# BQSandBox.net
KiCad netlist of a schematic drawn in Altium Designer
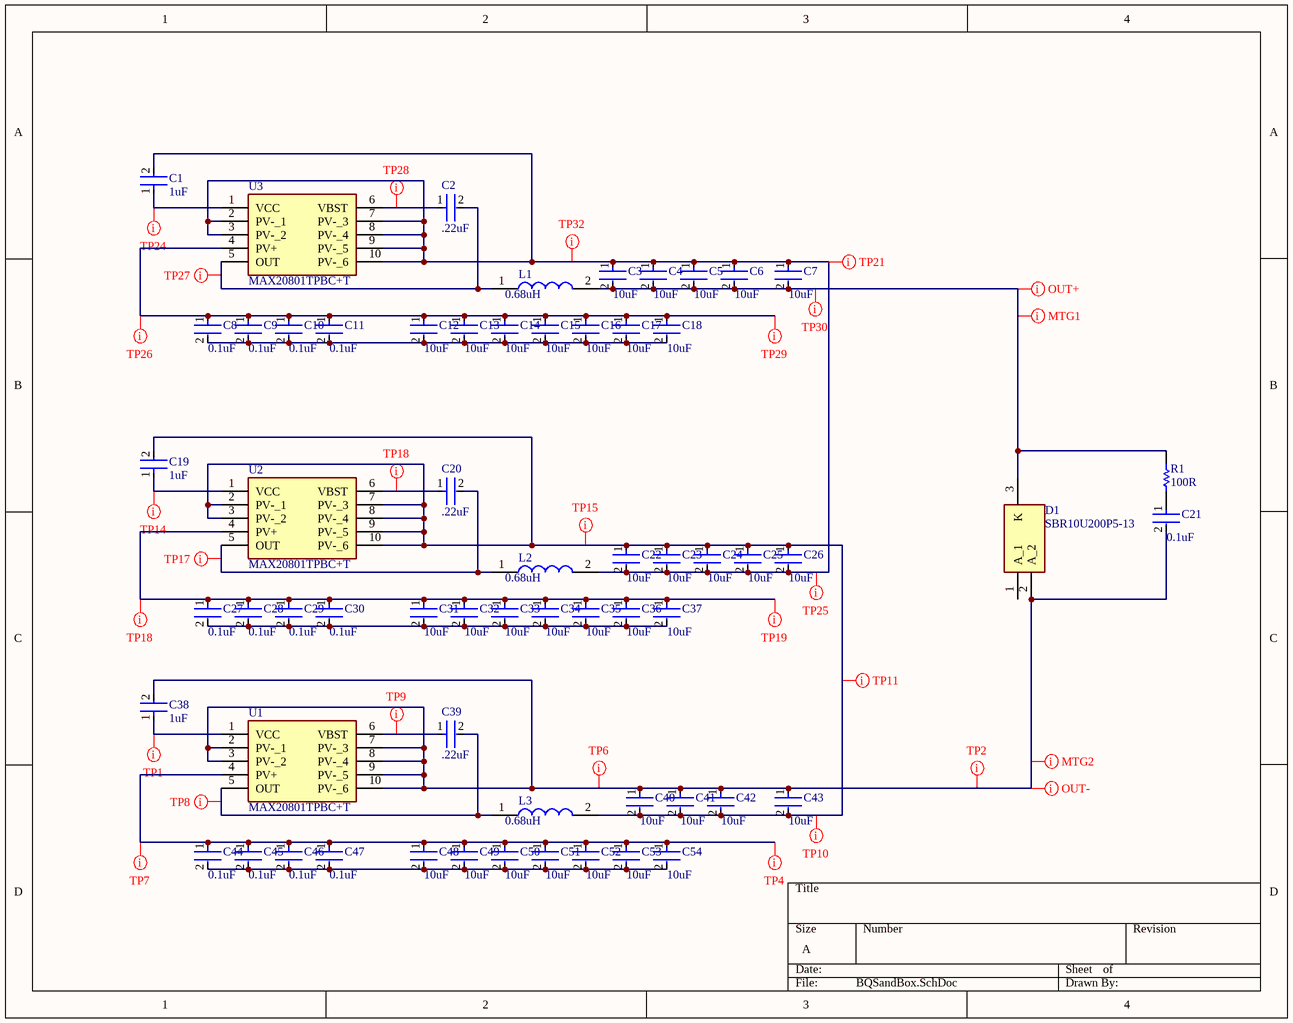
[diagram p0: BQSandBox.SchDoc]

(export (version "E")
  (design (tool "Eeschema 10.0.6"))
  (components
    (comp (ref "C1")
      (value "1uF")
      (footprint "FP-C0805C-DN-IPC_A")
      (description "Cap Ceramic 1uF 16V X5R 10% SMD 0805 85C Plastic T/R")
      (fields
        (field (name "MANUFACTURER") "KEMET")
        (field (name "MANUFACTURER PART NUMBER") "C0805C105K4PACTU")
      )
      (libsource (lib "WEST_Schematic_Library") (part "C0805C105K4PACTU"))
    )
    (comp (ref "C2")
      (value ".22uF")
      (footprint "FP-C0805C-DN-MFG")
      (description "C0805 0.22 μF X7R 30ppm/°C 10.00% 50 V")
      (fields (field (name "MANUFACTURER") "KEMET"))
      (libsource (lib "Altium Content Vault") (part "b4654b650e69147ec39a6b967a45e02"))
    )
    (comp (ref "C3")
      (value "10uF")
      (footprint "FP-C0805C-DN-IPC_A")
      (description "贴片电容（MLCC） 10μF ±10% 16V X5R 0805")
      (fields
        (field (name "MANUFACTURER") "Murata")
        (field (name "MANUFACTURER PART NUMBER") "GRM21BR61C106KE15L")
      )
      (libsource (lib "WEST_Schematic_Library") (part "GRM21BR61C106KE15L"))
    )
    (comp (ref "C4")
      (value "10uF")
      (footprint "FP-C0805C-DN-IPC_A")
      (description "贴片电容（MLCC） 10μF ±10% 16V X5R 0805")
      (fields
        (field (name "MANUFACTURER") "Murata")
        (field (name "MANUFACTURER PART NUMBER") "GRM21BR61C106KE15L")
      )
      (libsource (lib "WEST_Schematic_Library") (part "GRM21BR61C106KE15L"))
    )
    (comp (ref "C5")
      (value "10uF")
      (footprint "FP-C0805C-DN-IPC_A")
      (description "贴片电容（MLCC） 10μF ±10% 16V X5R 0805")
      (fields
        (field (name "MANUFACTURER") "Murata")
        (field (name "MANUFACTURER PART NUMBER") "GRM21BR61C106KE15L")
      )
      (libsource (lib "WEST_Schematic_Library") (part "GRM21BR61C106KE15L"))
    )
    (comp (ref "C6")
      (value "10uF")
      (footprint "FP-C0805C-DN-IPC_A")
      (description "贴片电容（MLCC） 10μF ±10% 16V X5R 0805")
      (fields
        (field (name "MANUFACTURER") "Murata")
        (field (name "MANUFACTURER PART NUMBER") "GRM21BR61C106KE15L")
      )
      (libsource (lib "WEST_Schematic_Library") (part "GRM21BR61C106KE15L"))
    )
    (comp (ref "C7")
      (value "10uF")
      (footprint "FP-C0805C-DN-IPC_A")
      (description "贴片电容（MLCC） 10μF ±10% 16V X5R 0805")
      (fields
        (field (name "MANUFACTURER") "Murata")
        (field (name "MANUFACTURER PART NUMBER") "GRM21BR61C106KE15L")
      )
      (libsource (lib "WEST_Schematic_Library") (part "GRM21BR61C106KE15L"))
    )
    (comp (ref "C8")
      (value "0.1uF")
      (footprint "FP-C0805C-DN-IPC_A")
      (description "Cap Ceramic 0.1uF 50V X7R 10% SMD 2.0 x 1.2 mm 125 C Paper T/R")
      (fields
        (field (name "MANUFACTURER") "KEMET")
        (field (name "MANUFACTURER PART NUMBER") "C0805C104K5RACTU")
      )
      (libsource (lib "WEST_Schematic_Library") (part "C0805C104K5RACTU"))
    )
    (comp (ref "C9")
      (value "0.1uF")
      (footprint "FP-C0805C-DN-IPC_A")
      (description "Cap Ceramic 0.1uF 50V X7R 10% SMD 2.0 x 1.2 mm 125 C Paper T/R")
      (fields
        (field (name "MANUFACTURER") "KEMET")
        (field (name "MANUFACTURER PART NUMBER") "C0805C104K5RACTU")
      )
      (libsource (lib "WEST_Schematic_Library") (part "C0805C104K5RACTU"))
    )
    (comp (ref "C10")
      (value "0.1uF")
      (footprint "FP-C0805C-DN-IPC_A")
      (description "Cap Ceramic 0.1uF 50V X7R 10% SMD 2.0 x 1.2 mm 125 C Paper T/R")
      (fields
        (field (name "MANUFACTURER") "KEMET")
        (field (name "MANUFACTURER PART NUMBER") "C0805C104K5RACTU")
      )
      (libsource (lib "WEST_Schematic_Library") (part "C0805C104K5RACTU"))
    )
    (comp (ref "C11")
      (value "0.1uF")
      (footprint "FP-C0805C-DN-IPC_A")
      (description "Cap Ceramic 0.1uF 50V X7R 10% SMD 2.0 x 1.2 mm 125 C Paper T/R")
      (fields
        (field (name "MANUFACTURER") "KEMET")
        (field (name "MANUFACTURER PART NUMBER") "C0805C104K5RACTU")
      )
      (libsource (lib "WEST_Schematic_Library") (part "C0805C104K5RACTU"))
    )
    (comp (ref "C12")
      (value "10uF")
      (footprint "FP-C0805C-DN-IPC_A")
      (description "贴片电容（MLCC） 10μF ±10% 16V X5R 0805")
      (fields
        (field (name "MANUFACTURER") "Murata")
        (field (name "MANUFACTURER PART NUMBER") "GRM21BR61C106KE15L")
      )
      (libsource (lib "WEST_Schematic_Library") (part "GRM21BR61C106KE15L"))
    )
    (comp (ref "C13")
      (value "10uF")
      (footprint "FP-C0805C-DN-IPC_A")
      (description "贴片电容（MLCC） 10μF ±10% 16V X5R 0805")
      (fields
        (field (name "MANUFACTURER") "Murata")
        (field (name "MANUFACTURER PART NUMBER") "GRM21BR61C106KE15L")
      )
      (libsource (lib "WEST_Schematic_Library") (part "GRM21BR61C106KE15L"))
    )
    (comp (ref "C14")
      (value "10uF")
      (footprint "FP-C0805C-DN-IPC_A")
      (description "贴片电容（MLCC） 10μF ±10% 16V X5R 0805")
      (fields
        (field (name "MANUFACTURER") "Murata")
        (field (name "MANUFACTURER PART NUMBER") "GRM21BR61C106KE15L")
      )
      (libsource (lib "WEST_Schematic_Library") (part "GRM21BR61C106KE15L"))
    )
    (comp (ref "C15")
      (value "10uF")
      (footprint "FP-C0805C-DN-IPC_A")
      (description "贴片电容（MLCC） 10μF ±10% 16V X5R 0805")
      (fields
        (field (name "MANUFACTURER") "Murata")
        (field (name "MANUFACTURER PART NUMBER") "GRM21BR61C106KE15L")
      )
      (libsource (lib "WEST_Schematic_Library") (part "GRM21BR61C106KE15L"))
    )
    (comp (ref "C16")
      (value "10uF")
      (footprint "FP-C0805C-DN-IPC_A")
      (description "贴片电容（MLCC） 10μF ±10% 16V X5R 0805")
      (fields
        (field (name "MANUFACTURER") "Murata")
        (field (name "MANUFACTURER PART NUMBER") "GRM21BR61C106KE15L")
      )
      (libsource (lib "WEST_Schematic_Library") (part "GRM21BR61C106KE15L"))
    )
    (comp (ref "C17")
      (value "10uF")
      (footprint "FP-C0805C-DN-IPC_A")
      (description "贴片电容（MLCC） 10μF ±10% 16V X5R 0805")
      (fields
        (field (name "MANUFACTURER") "Murata")
        (field (name "MANUFACTURER PART NUMBER") "GRM21BR61C106KE15L")
      )
      (libsource (lib "WEST_Schematic_Library") (part "GRM21BR61C106KE15L"))
    )
    (comp (ref "C18")
      (value "10uF")
      (footprint "FP-C0805C-DN-IPC_A")
      (description "贴片电容（MLCC） 10μF ±10% 16V X5R 0805")
      (fields
        (field (name "MANUFACTURER") "Murata")
        (field (name "MANUFACTURER PART NUMBER") "GRM21BR61C106KE15L")
      )
      (libsource (lib "WEST_Schematic_Library") (part "GRM21BR61C106KE15L"))
    )
    (comp (ref "C19")
      (value "1uF")
      (footprint "FP-C0805C-DN-IPC_A")
      (description "Cap Ceramic 1uF 16V X5R 10% SMD 0805 85C Plastic T/R")
      (fields
        (field (name "MANUFACTURER") "KEMET")
        (field (name "MANUFACTURER PART NUMBER") "C0805C105K4PACTU")
      )
      (libsource (lib "WEST_Schematic_Library") (part "C0805C105K4PACTU"))
    )
    (comp (ref "C20")
      (value ".22uF")
      (footprint "FP-C0805C-DN-MFG")
      (description "C0805 0.22 μF X7R 30ppm/°C 10.00% 50 V")
      (fields (field (name "MANUFACTURER") "KEMET"))
      (libsource (lib "Altium Content Vault") (part "b4654b650e69147ec39a6b967a45e02"))
    )
    (comp (ref "C21")
      (value "0.1uF")
      (footprint "FP-C0805C-DN-IPC_A")
      (description "Cap Ceramic 0.1uF 50V X7R 10% SMD 2.0 x 1.2 mm 125 C Paper T/R")
      (fields
        (field (name "MANUFACTURER") "KEMET")
        (field (name "MANUFACTURER PART NUMBER") "C0805C104K5RACTU")
      )
      (libsource (lib "WEST_Schematic_Library") (part "C0805C104K5RACTU"))
    )
    (comp (ref "C22")
      (value "10uF")
      (footprint "FP-C0805C-DN-IPC_A")
      (description "贴片电容（MLCC） 10μF ±10% 16V X5R 0805")
      (fields
        (field (name "MANUFACTURER") "Murata")
        (field (name "MANUFACTURER PART NUMBER") "GRM21BR61C106KE15L")
      )
      (libsource (lib "WEST_Schematic_Library") (part "GRM21BR61C106KE15L"))
    )
    (comp (ref "C23")
      (value "10uF")
      (footprint "FP-C0805C-DN-IPC_A")
      (description "贴片电容（MLCC） 10μF ±10% 16V X5R 0805")
      (fields
        (field (name "MANUFACTURER") "Murata")
        (field (name "MANUFACTURER PART NUMBER") "GRM21BR61C106KE15L")
      )
      (libsource (lib "WEST_Schematic_Library") (part "GRM21BR61C106KE15L"))
    )
    (comp (ref "C24")
      (value "10uF")
      (footprint "FP-C0805C-DN-IPC_A")
      (description "贴片电容（MLCC） 10μF ±10% 16V X5R 0805")
      (fields
        (field (name "MANUFACTURER") "Murata")
        (field (name "MANUFACTURER PART NUMBER") "GRM21BR61C106KE15L")
      )
      (libsource (lib "WEST_Schematic_Library") (part "GRM21BR61C106KE15L"))
    )
    (comp (ref "C25")
      (value "10uF")
      (footprint "FP-C0805C-DN-IPC_A")
      (description "贴片电容（MLCC） 10μF ±10% 16V X5R 0805")
      (fields
        (field (name "MANUFACTURER") "Murata")
        (field (name "MANUFACTURER PART NUMBER") "GRM21BR61C106KE15L")
      )
      (libsource (lib "WEST_Schematic_Library") (part "GRM21BR61C106KE15L"))
    )
    (comp (ref "C26")
      (value "10uF")
      (footprint "FP-C0805C-DN-IPC_A")
      (description "贴片电容（MLCC） 10μF ±10% 16V X5R 0805")
      (fields
        (field (name "MANUFACTURER") "Murata")
        (field (name "MANUFACTURER PART NUMBER") "GRM21BR61C106KE15L")
      )
      (libsource (lib "WEST_Schematic_Library") (part "GRM21BR61C106KE15L"))
    )
    (comp (ref "C27")
      (value "0.1uF")
      (footprint "FP-C0805C-DN-IPC_A")
      (description "Cap Ceramic 0.1uF 50V X7R 10% SMD 2.0 x 1.2 mm 125 C Paper T/R")
      (fields
        (field (name "MANUFACTURER") "KEMET")
        (field (name "MANUFACTURER PART NUMBER") "C0805C104K5RACTU")
      )
      (libsource (lib "WEST_Schematic_Library") (part "C0805C104K5RACTU"))
    )
    (comp (ref "C28")
      (value "0.1uF")
      (footprint "FP-C0805C-DN-IPC_A")
      (description "Cap Ceramic 0.1uF 50V X7R 10% SMD 2.0 x 1.2 mm 125 C Paper T/R")
      (fields
        (field (name "MANUFACTURER") "KEMET")
        (field (name "MANUFACTURER PART NUMBER") "C0805C104K5RACTU")
      )
      (libsource (lib "WEST_Schematic_Library") (part "C0805C104K5RACTU"))
    )
    (comp (ref "C29")
      (value "0.1uF")
      (footprint "FP-C0805C-DN-IPC_A")
      (description "Cap Ceramic 0.1uF 50V X7R 10% SMD 2.0 x 1.2 mm 125 C Paper T/R")
      (fields
        (field (name "MANUFACTURER") "KEMET")
        (field (name "MANUFACTURER PART NUMBER") "C0805C104K5RACTU")
      )
      (libsource (lib "WEST_Schematic_Library") (part "C0805C104K5RACTU"))
    )
    (comp (ref "C30")
      (value "0.1uF")
      (footprint "FP-C0805C-DN-IPC_A")
      (description "Cap Ceramic 0.1uF 50V X7R 10% SMD 2.0 x 1.2 mm 125 C Paper T/R")
      (fields
        (field (name "MANUFACTURER") "KEMET")
        (field (name "MANUFACTURER PART NUMBER") "C0805C104K5RACTU")
      )
      (libsource (lib "WEST_Schematic_Library") (part "C0805C104K5RACTU"))
    )
    (comp (ref "C31")
      (value "10uF")
      (footprint "FP-C0805C-DN-IPC_A")
      (description "贴片电容（MLCC） 10μF ±10% 16V X5R 0805")
      (fields
        (field (name "MANUFACTURER") "Murata")
        (field (name "MANUFACTURER PART NUMBER") "GRM21BR61C106KE15L")
      )
      (libsource (lib "WEST_Schematic_Library") (part "GRM21BR61C106KE15L"))
    )
    (comp (ref "C32")
      (value "10uF")
      (footprint "FP-C0805C-DN-IPC_A")
      (description "贴片电容（MLCC） 10μF ±10% 16V X5R 0805")
      (fields
        (field (name "MANUFACTURER") "Murata")
        (field (name "MANUFACTURER PART NUMBER") "GRM21BR61C106KE15L")
      )
      (libsource (lib "WEST_Schematic_Library") (part "GRM21BR61C106KE15L"))
    )
    (comp (ref "C33")
      (value "10uF")
      (footprint "FP-C0805C-DN-IPC_A")
      (description "贴片电容（MLCC） 10μF ±10% 16V X5R 0805")
      (fields
        (field (name "MANUFACTURER") "Murata")
        (field (name "MANUFACTURER PART NUMBER") "GRM21BR61C106KE15L")
      )
      (libsource (lib "WEST_Schematic_Library") (part "GRM21BR61C106KE15L"))
    )
    (comp (ref "C34")
      (value "10uF")
      (footprint "FP-C0805C-DN-IPC_A")
      (description "贴片电容（MLCC） 10μF ±10% 16V X5R 0805")
      (fields
        (field (name "MANUFACTURER") "Murata")
        (field (name "MANUFACTURER PART NUMBER") "GRM21BR61C106KE15L")
      )
      (libsource (lib "WEST_Schematic_Library") (part "GRM21BR61C106KE15L"))
    )
    (comp (ref "C35")
      (value "10uF")
      (footprint "FP-C0805C-DN-IPC_A")
      (description "贴片电容（MLCC） 10μF ±10% 16V X5R 0805")
      (fields
        (field (name "MANUFACTURER") "Murata")
        (field (name "MANUFACTURER PART NUMBER") "GRM21BR61C106KE15L")
      )
      (libsource (lib "WEST_Schematic_Library") (part "GRM21BR61C106KE15L"))
    )
    (comp (ref "C36")
      (value "10uF")
      (footprint "FP-C0805C-DN-IPC_A")
      (description "贴片电容（MLCC） 10μF ±10% 16V X5R 0805")
      (fields
        (field (name "MANUFACTURER") "Murata")
        (field (name "MANUFACTURER PART NUMBER") "GRM21BR61C106KE15L")
      )
      (libsource (lib "WEST_Schematic_Library") (part "GRM21BR61C106KE15L"))
    )
    (comp (ref "C37")
      (value "10uF")
      (footprint "FP-C0805C-DN-IPC_A")
      (description "贴片电容（MLCC） 10μF ±10% 16V X5R 0805")
      (fields
        (field (name "MANUFACTURER") "Murata")
        (field (name "MANUFACTURER PART NUMBER") "GRM21BR61C106KE15L")
      )
      (libsource (lib "WEST_Schematic_Library") (part "GRM21BR61C106KE15L"))
    )
    (comp (ref "C38")
      (value "1uF")
      (footprint "FP-C0805C-DN-IPC_A")
      (description "Cap Ceramic 1uF 16V X5R 10% SMD 0805 85C Plastic T/R")
      (fields
        (field (name "MANUFACTURER") "KEMET")
        (field (name "MANUFACTURER PART NUMBER") "C0805C105K4PACTU")
      )
      (libsource (lib "WEST_Schematic_Library") (part "C0805C105K4PACTU"))
    )
    (comp (ref "C39")
      (value ".22uF")
      (footprint "FP-C0805C-DN-MFG")
      (description "C0805 0.22 μF X7R 30ppm/°C 10.00% 50 V")
      (fields (field (name "MANUFACTURER") "KEMET"))
      (libsource (lib "Altium Content Vault") (part "b4654b650e69147ec39a6b967a45e02"))
    )
    (comp (ref "C40")
      (value "10uF")
      (footprint "FP-C0805C-DN-IPC_A")
      (description "贴片电容（MLCC） 10μF ±10% 16V X5R 0805")
      (fields
        (field (name "MANUFACTURER") "Murata")
        (field (name "MANUFACTURER PART NUMBER") "GRM21BR61C106KE15L")
      )
      (libsource (lib "WEST_Schematic_Library") (part "GRM21BR61C106KE15L"))
    )
    (comp (ref "C41")
      (value "10uF")
      (footprint "FP-C0805C-DN-IPC_A")
      (description "贴片电容（MLCC） 10μF ±10% 16V X5R 0805")
      (fields
        (field (name "MANUFACTURER") "Murata")
        (field (name "MANUFACTURER PART NUMBER") "GRM21BR61C106KE15L")
      )
      (libsource (lib "WEST_Schematic_Library") (part "GRM21BR61C106KE15L"))
    )
    (comp (ref "C42")
      (value "10uF")
      (footprint "FP-C0805C-DN-IPC_A")
      (description "贴片电容（MLCC） 10μF ±10% 16V X5R 0805")
      (fields
        (field (name "MANUFACTURER") "Murata")
        (field (name "MANUFACTURER PART NUMBER") "GRM21BR61C106KE15L")
      )
      (libsource (lib "WEST_Schematic_Library") (part "GRM21BR61C106KE15L"))
    )
    (comp (ref "C43")
      (value "10uF")
      (footprint "FP-C0805C-DN-IPC_A")
      (description "贴片电容（MLCC） 10μF ±10% 16V X5R 0805")
      (fields
        (field (name "MANUFACTURER") "Murata")
        (field (name "MANUFACTURER PART NUMBER") "GRM21BR61C106KE15L")
      )
      (libsource (lib "WEST_Schematic_Library") (part "GRM21BR61C106KE15L"))
    )
    (comp (ref "C44")
      (value "0.1uF")
      (footprint "FP-C0805C-DN-IPC_A")
      (description "Cap Ceramic 0.1uF 50V X7R 10% SMD 2.0 x 1.2 mm 125 C Paper T/R")
      (fields
        (field (name "MANUFACTURER") "KEMET")
        (field (name "MANUFACTURER PART NUMBER") "C0805C104K5RACTU")
      )
      (libsource (lib "WEST_Schematic_Library") (part "C0805C104K5RACTU"))
    )
    (comp (ref "C45")
      (value "0.1uF")
      (footprint "FP-C0805C-DN-IPC_A")
      (description "Cap Ceramic 0.1uF 50V X7R 10% SMD 2.0 x 1.2 mm 125 C Paper T/R")
      (fields
        (field (name "MANUFACTURER") "KEMET")
        (field (name "MANUFACTURER PART NUMBER") "C0805C104K5RACTU")
      )
      (libsource (lib "WEST_Schematic_Library") (part "C0805C104K5RACTU"))
    )
    (comp (ref "C46")
      (value "0.1uF")
      (footprint "FP-C0805C-DN-IPC_A")
      (description "Cap Ceramic 0.1uF 50V X7R 10% SMD 2.0 x 1.2 mm 125 C Paper T/R")
      (fields
        (field (name "MANUFACTURER") "KEMET")
        (field (name "MANUFACTURER PART NUMBER") "C0805C104K5RACTU")
      )
      (libsource (lib "WEST_Schematic_Library") (part "C0805C104K5RACTU"))
    )
    (comp (ref "C47")
      (value "0.1uF")
      (footprint "FP-C0805C-DN-IPC_A")
      (description "Cap Ceramic 0.1uF 50V X7R 10% SMD 2.0 x 1.2 mm 125 C Paper T/R")
      (fields
        (field (name "MANUFACTURER") "KEMET")
        (field (name "MANUFACTURER PART NUMBER") "C0805C104K5RACTU")
      )
      (libsource (lib "WEST_Schematic_Library") (part "C0805C104K5RACTU"))
    )
    (comp (ref "C48")
      (value "10uF")
      (footprint "FP-C0805C-DN-IPC_A")
      (description "贴片电容（MLCC） 10μF ±10% 16V X5R 0805")
      (fields
        (field (name "MANUFACTURER") "Murata")
        (field (name "MANUFACTURER PART NUMBER") "GRM21BR61C106KE15L")
      )
      (libsource (lib "WEST_Schematic_Library") (part "GRM21BR61C106KE15L"))
    )
    (comp (ref "C49")
      (value "10uF")
      (footprint "FP-C0805C-DN-IPC_A")
      (description "贴片电容（MLCC） 10μF ±10% 16V X5R 0805")
      (fields
        (field (name "MANUFACTURER") "Murata")
        (field (name "MANUFACTURER PART NUMBER") "GRM21BR61C106KE15L")
      )
      (libsource (lib "WEST_Schematic_Library") (part "GRM21BR61C106KE15L"))
    )
    (comp (ref "C50")
      (value "10uF")
      (footprint "FP-C0805C-DN-IPC_A")
      (description "贴片电容（MLCC） 10μF ±10% 16V X5R 0805")
      (fields
        (field (name "MANUFACTURER") "Murata")
        (field (name "MANUFACTURER PART NUMBER") "GRM21BR61C106KE15L")
      )
      (libsource (lib "WEST_Schematic_Library") (part "GRM21BR61C106KE15L"))
    )
    (comp (ref "C51")
      (value "10uF")
      (footprint "FP-C0805C-DN-IPC_A")
      (description "贴片电容（MLCC） 10μF ±10% 16V X5R 0805")
      (fields
        (field (name "MANUFACTURER") "Murata")
        (field (name "MANUFACTURER PART NUMBER") "GRM21BR61C106KE15L")
      )
      (libsource (lib "WEST_Schematic_Library") (part "GRM21BR61C106KE15L"))
    )
    (comp (ref "C52")
      (value "10uF")
      (footprint "FP-C0805C-DN-IPC_A")
      (description "贴片电容（MLCC） 10μF ±10% 16V X5R 0805")
      (fields
        (field (name "MANUFACTURER") "Murata")
        (field (name "MANUFACTURER PART NUMBER") "GRM21BR61C106KE15L")
      )
      (libsource (lib "WEST_Schematic_Library") (part "GRM21BR61C106KE15L"))
    )
    (comp (ref "C53")
      (value "10uF")
      (footprint "FP-C0805C-DN-IPC_A")
      (description "贴片电容（MLCC） 10μF ±10% 16V X5R 0805")
      (fields
        (field (name "MANUFACTURER") "Murata")
        (field (name "MANUFACTURER PART NUMBER") "GRM21BR61C106KE15L")
      )
      (libsource (lib "WEST_Schematic_Library") (part "GRM21BR61C106KE15L"))
    )
    (comp (ref "C54")
      (value "10uF")
      (footprint "FP-C0805C-DN-IPC_A")
      (description "贴片电容（MLCC） 10μF ±10% 16V X5R 0805")
      (fields
        (field (name "MANUFACTURER") "Murata")
        (field (name "MANUFACTURER PART NUMBER") "GRM21BR61C106KE15L")
      )
      (libsource (lib "WEST_Schematic_Library") (part "GRM21BR61C106KE15L"))
    )
    (comp (ref "D1")
      (value "SBR10U200P5-13")
      (footprint "SamacSys:SBR10U200P513")
      (description "Diode")
      (libsource (lib "SamacSys") (part "SBR10U200P5-13"))
    )
    (comp (ref "L1")
      (value "0.68uH")
      (footprint "SamacSys:INDPM6965X300N")
      (description "Inductor")
      (fields
        (field (name "MANUFACTURER_PART_NUMBER") "IHLP2525CZERR47M01")
        (field (name "MOUSER PART NUMBER") "70-IHLP2525CZERR47M1")
      )
      (libsource (lib "SamacSys") (part "IHLP2525CZERR47M01"))
    )
    (comp (ref "L2")
      (value "0.68uH")
      (footprint "SamacSys:INDPM6965X300N")
      (description "Inductor")
      (fields
        (field (name "MANUFACTURER_PART_NUMBER") "IHLP2525CZERR47M01")
        (field (name "MOUSER PART NUMBER") "70-IHLP2525CZERR47M1")
      )
      (libsource (lib "SamacSys") (part "IHLP2525CZERR47M01"))
    )
    (comp (ref "L3")
      (value "0.68uH")
      (footprint "SamacSys:INDPM6965X300N")
      (description "Inductor")
      (fields
        (field (name "MANUFACTURER_PART_NUMBER") "IHLP2525CZERR47M01")
        (field (name "MOUSER PART NUMBER") "70-IHLP2525CZERR47M1")
      )
      (libsource (lib "SamacSys") (part "IHLP2525CZERR47M01"))
    )
    (comp (ref "R1")
      (value "100R")
      (footprint "FP-C0805C-DN-IPC_A")
      (description "贴片电阻 100Ω ±1% 1/8W ±100ppm/℃ 0805")
      (fields
        (field (name "MANUFACTURER") "Panasonic")
        (field (name "MANUFACTURER PART NUMBER") "ERJ-6ENF1000V")
      )
      (libsource (lib "WEST_Schematic_Library") (part "ERJ-6ENF1000V"))
    )
    (comp (ref "U1")
      (value "MAX20801TPBC+T")
      (footprint "SamacSys:MAX20801TPBC")
      (description "Integrated Circuit")
      (libsource (lib "SamacSys") (part "MAX20801TPBC+T"))
    )
    (comp (ref "U2")
      (value "MAX20801TPBC+T")
      (footprint "SamacSys:MAX20801TPBC")
      (description "Integrated Circuit")
      (libsource (lib "SamacSys") (part "MAX20801TPBC+T"))
    )
    (comp (ref "U3")
      (value "MAX20801TPBC+T")
      (footprint "SamacSys:MAX20801TPBC")
      (description "Integrated Circuit")
      (libsource (lib "SamacSys") (part "MAX20801TPBC+T"))
    )
  )
  (nets
    (net (code "1") (name "Net-(C10-Pad2)") (class "Default")
      (node (ref "C10") (pin "2") (pinfunction "2_2") (pintype "passive"))
      (node (ref "C11") (pin "2") (pinfunction "2_2") (pintype "passive"))
      (node (ref "C12") (pin "2") (pinfunction "2_2") (pintype "passive"))
      (node (ref "C13") (pin "2") (pinfunction "2_2") (pintype "passive"))
      (node (ref "C14") (pin "2") (pinfunction "2_2") (pintype "passive"))
      (node (ref "C15") (pin "2") (pinfunction "2_2") (pintype "passive"))
      (node (ref "C16") (pin "2") (pinfunction "2_2") (pintype "passive"))
      (node (ref "C17") (pin "2") (pinfunction "2_2") (pintype "passive"))
      (node (ref "C18") (pin "2") (pinfunction "2_2") (pintype "passive"))
      (node (ref "C8") (pin "2") (pinfunction "2_2") (pintype "passive"))
      (node (ref "C9") (pin "2") (pinfunction "2_2") (pintype "passive"))
    )
    (net (code "2") (name "Net-(C21-Pad1)") (class "Default")
      (node (ref "C21") (pin "1") (pinfunction "1_1") (pintype "passive"))
      (node (ref "R1") (pin "1") (pinfunction "1_1") (pintype "passive"))
    )
    (net (code "3") (name "Net-(C27-Pad2)") (class "Default")
      (node (ref "C27") (pin "2") (pinfunction "2_2") (pintype "passive"))
      (node (ref "C28") (pin "2") (pinfunction "2_2") (pintype "passive"))
      (node (ref "C29") (pin "2") (pinfunction "2_2") (pintype "passive"))
      (node (ref "C30") (pin "2") (pinfunction "2_2") (pintype "passive"))
      (node (ref "C31") (pin "2") (pinfunction "2_2") (pintype "passive"))
      (node (ref "C32") (pin "2") (pinfunction "2_2") (pintype "passive"))
      (node (ref "C33") (pin "2") (pinfunction "2_2") (pintype "passive"))
      (node (ref "C34") (pin "2") (pinfunction "2_2") (pintype "passive"))
      (node (ref "C35") (pin "2") (pinfunction "2_2") (pintype "passive"))
      (node (ref "C36") (pin "2") (pinfunction "2_2") (pintype "passive"))
      (node (ref "C37") (pin "2") (pinfunction "2_2") (pintype "passive"))
    )
    (net (code "4") (name "Net-(C44-Pad2)") (class "Default")
      (node (ref "C44") (pin "2") (pinfunction "2_2") (pintype "passive"))
      (node (ref "C45") (pin "2") (pinfunction "2_2") (pintype "passive"))
      (node (ref "C46") (pin "2") (pinfunction "2_2") (pintype "passive"))
      (node (ref "C47") (pin "2") (pinfunction "2_2") (pintype "passive"))
      (node (ref "C48") (pin "2") (pinfunction "2_2") (pintype "passive"))
      (node (ref "C49") (pin "2") (pinfunction "2_2") (pintype "passive"))
      (node (ref "C50") (pin "2") (pinfunction "2_2") (pintype "passive"))
      (node (ref "C51") (pin "2") (pinfunction "2_2") (pintype "passive"))
      (node (ref "C52") (pin "2") (pinfunction "2_2") (pintype "passive"))
      (node (ref "C53") (pin "2") (pinfunction "2_2") (pintype "passive"))
      (node (ref "C54") (pin "2") (pinfunction "2_2") (pintype "passive"))
    )
    (net (code "5") (name "Net-(D1-A_2)") (class "Default")
      (node (ref "C21") (pin "2") (pinfunction "2_2") (pintype "passive"))
      (node (ref "C38") (pin "2") (pinfunction "2_2") (pintype "passive"))
      (node (ref "C40") (pin "1") (pinfunction "1_1") (pintype "passive"))
      (node (ref "C41") (pin "1") (pinfunction "1_1") (pintype "passive"))
      (node (ref "C42") (pin "1") (pinfunction "1_1") (pintype "passive"))
      (node (ref "C43") (pin "1") (pinfunction "1_1") (pintype "passive"))
      (node (ref "D1") (pin "2") (pinfunction "A_2_2") (pintype "passive"))
      (node (ref "U1") (pin "10") (pinfunction "PV-_6_10") (pintype "passive"))
      (node (ref "U1") (pin "2") (pinfunction "PV-_1_2") (pintype "passive"))
      (node (ref "U1") (pin "3") (pinfunction "PV-_2_3") (pintype "passive"))
      (node (ref "U1") (pin "7") (pinfunction "PV-_3_7") (pintype "passive"))
      (node (ref "U1") (pin "8") (pinfunction "PV-_4_8") (pintype "passive"))
      (node (ref "U1") (pin "9") (pinfunction "PV-_5_9") (pintype "passive"))
    )
    (net (code "6") (name "Net-(D1-K)") (class "Default")
      (node (ref "C3") (pin "2") (pinfunction "2_2") (pintype "passive"))
      (node (ref "C4") (pin "2") (pinfunction "2_2") (pintype "passive"))
      (node (ref "C5") (pin "2") (pinfunction "2_2") (pintype "passive"))
      (node (ref "C6") (pin "2") (pinfunction "2_2") (pintype "passive"))
      (node (ref "C7") (pin "2") (pinfunction "2_2") (pintype "passive"))
      (node (ref "D1") (pin "3") (pinfunction "K_3") (pintype "passive"))
      (node (ref "L1") (pin "2") (pinfunction "2_2") (pintype "passive"))
      (node (ref "R1") (pin "2") (pinfunction "2_2") (pintype "passive"))
    )
    (net (code "7") (name "Net-(U1-OUT)") (class "Default")
      (node (ref "C39") (pin "2") (pinfunction "2_2") (pintype "passive"))
      (node (ref "L3") (pin "1") (pinfunction "1_1") (pintype "passive"))
      (node (ref "U1") (pin "5") (pinfunction "OUT_5") (pintype "passive"))
    )
    (net (code "8") (name "Net-(U1-PV+)") (class "Default")
      (node (ref "C44") (pin "1") (pinfunction "1_1") (pintype "passive"))
      (node (ref "C45") (pin "1") (pinfunction "1_1") (pintype "passive"))
      (node (ref "C46") (pin "1") (pinfunction "1_1") (pintype "passive"))
      (node (ref "C47") (pin "1") (pinfunction "1_1") (pintype "passive"))
      (node (ref "C48") (pin "1") (pinfunction "1_1") (pintype "passive"))
      (node (ref "C49") (pin "1") (pinfunction "1_1") (pintype "passive"))
      (node (ref "C50") (pin "1") (pinfunction "1_1") (pintype "passive"))
      (node (ref "C51") (pin "1") (pinfunction "1_1") (pintype "passive"))
      (node (ref "C52") (pin "1") (pinfunction "1_1") (pintype "passive"))
      (node (ref "C53") (pin "1") (pinfunction "1_1") (pintype "passive"))
      (node (ref "C54") (pin "1") (pinfunction "1_1") (pintype "passive"))
      (node (ref "U1") (pin "4") (pinfunction "PV+_4") (pintype "passive"))
    )
    (net (code "9") (name "Net-(U1-VBST)") (class "Default")
      (node (ref "C39") (pin "1") (pinfunction "1_1") (pintype "passive"))
      (node (ref "U1") (pin "6") (pinfunction "VBST_6") (pintype "passive"))
    )
    (net (code "10") (name "Net-(U1-VCC)") (class "Default")
      (node (ref "C38") (pin "1") (pinfunction "1_1") (pintype "passive"))
      (node (ref "U1") (pin "1") (pinfunction "VCC_1") (pintype "passive"))
    )
    (net (code "11") (name "Net-(U2-OUT)") (class "Default")
      (node (ref "C20") (pin "2") (pinfunction "2_2") (pintype "passive"))
      (node (ref "L2") (pin "1") (pinfunction "1_1") (pintype "passive"))
      (node (ref "U2") (pin "5") (pinfunction "OUT_5") (pintype "passive"))
    )
    (net (code "12") (name "Net-(U2-PV+)") (class "Default")
      (node (ref "C27") (pin "1") (pinfunction "1_1") (pintype "passive"))
      (node (ref "C28") (pin "1") (pinfunction "1_1") (pintype "passive"))
      (node (ref "C29") (pin "1") (pinfunction "1_1") (pintype "passive"))
      (node (ref "C30") (pin "1") (pinfunction "1_1") (pintype "passive"))
      (node (ref "C31") (pin "1") (pinfunction "1_1") (pintype "passive"))
      (node (ref "C32") (pin "1") (pinfunction "1_1") (pintype "passive"))
      (node (ref "C33") (pin "1") (pinfunction "1_1") (pintype "passive"))
      (node (ref "C34") (pin "1") (pinfunction "1_1") (pintype "passive"))
      (node (ref "C35") (pin "1") (pinfunction "1_1") (pintype "passive"))
      (node (ref "C36") (pin "1") (pinfunction "1_1") (pintype "passive"))
      (node (ref "C37") (pin "1") (pinfunction "1_1") (pintype "passive"))
      (node (ref "U2") (pin "4") (pinfunction "PV+_4") (pintype "passive"))
    )
    (net (code "13") (name "Net-(U2-PV-_1)") (class "Default")
      (node (ref "C19") (pin "2") (pinfunction "2_2") (pintype "passive"))
      (node (ref "C22") (pin "1") (pinfunction "1_1") (pintype "passive"))
      (node (ref "C23") (pin "1") (pinfunction "1_1") (pintype "passive"))
      (node (ref "C24") (pin "1") (pinfunction "1_1") (pintype "passive"))
      (node (ref "C25") (pin "1") (pinfunction "1_1") (pintype "passive"))
      (node (ref "C26") (pin "1") (pinfunction "1_1") (pintype "passive"))
      (node (ref "C40") (pin "2") (pinfunction "2_2") (pintype "passive"))
      (node (ref "C41") (pin "2") (pinfunction "2_2") (pintype "passive"))
      (node (ref "C42") (pin "2") (pinfunction "2_2") (pintype "passive"))
      (node (ref "C43") (pin "2") (pinfunction "2_2") (pintype "passive"))
      (node (ref "L3") (pin "2") (pinfunction "2_2") (pintype "passive"))
      (node (ref "U2") (pin "10") (pinfunction "PV-_6_10") (pintype "passive"))
      (node (ref "U2") (pin "2") (pinfunction "PV-_1_2") (pintype "passive"))
      (node (ref "U2") (pin "3") (pinfunction "PV-_2_3") (pintype "passive"))
      (node (ref "U2") (pin "7") (pinfunction "PV-_3_7") (pintype "passive"))
      (node (ref "U2") (pin "8") (pinfunction "PV-_4_8") (pintype "passive"))
      (node (ref "U2") (pin "9") (pinfunction "PV-_5_9") (pintype "passive"))
    )
    (net (code "14") (name "Net-(U2-VBST)") (class "Default")
      (node (ref "C20") (pin "1") (pinfunction "1_1") (pintype "passive"))
      (node (ref "U2") (pin "6") (pinfunction "VBST_6") (pintype "passive"))
    )
    (net (code "15") (name "Net-(U2-VCC)") (class "Default")
      (node (ref "C19") (pin "1") (pinfunction "1_1") (pintype "passive"))
      (node (ref "U2") (pin "1") (pinfunction "VCC_1") (pintype "passive"))
    )
    (net (code "16") (name "Net-(U3-OUT)") (class "Default")
      (node (ref "C2") (pin "2") (pinfunction "2_2") (pintype "passive"))
      (node (ref "L1") (pin "1") (pinfunction "1_1") (pintype "passive"))
      (node (ref "U3") (pin "5") (pinfunction "OUT_5") (pintype "passive"))
    )
    (net (code "17") (name "Net-(U3-PV+)") (class "Default")
      (node (ref "C10") (pin "1") (pinfunction "1_1") (pintype "passive"))
      (node (ref "C11") (pin "1") (pinfunction "1_1") (pintype "passive"))
      (node (ref "C12") (pin "1") (pinfunction "1_1") (pintype "passive"))
      (node (ref "C13") (pin "1") (pinfunction "1_1") (pintype "passive"))
      (node (ref "C14") (pin "1") (pinfunction "1_1") (pintype "passive"))
      (node (ref "C15") (pin "1") (pinfunction "1_1") (pintype "passive"))
      (node (ref "C16") (pin "1") (pinfunction "1_1") (pintype "passive"))
      (node (ref "C17") (pin "1") (pinfunction "1_1") (pintype "passive"))
      (node (ref "C18") (pin "1") (pinfunction "1_1") (pintype "passive"))
      (node (ref "C8") (pin "1") (pinfunction "1_1") (pintype "passive"))
      (node (ref "C9") (pin "1") (pinfunction "1_1") (pintype "passive"))
      (node (ref "U3") (pin "4") (pinfunction "PV+_4") (pintype "passive"))
    )
    (net (code "18") (name "Net-(U3-PV-_1)") (class "Default")
      (node (ref "C1") (pin "2") (pinfunction "2_2") (pintype "passive"))
      (node (ref "C22") (pin "2") (pinfunction "2_2") (pintype "passive"))
      (node (ref "C23") (pin "2") (pinfunction "2_2") (pintype "passive"))
      (node (ref "C24") (pin "2") (pinfunction "2_2") (pintype "passive"))
      (node (ref "C25") (pin "2") (pinfunction "2_2") (pintype "passive"))
      (node (ref "C26") (pin "2") (pinfunction "2_2") (pintype "passive"))
      (node (ref "C3") (pin "1") (pinfunction "1_1") (pintype "passive"))
      (node (ref "C4") (pin "1") (pinfunction "1_1") (pintype "passive"))
      (node (ref "C5") (pin "1") (pinfunction "1_1") (pintype "passive"))
      (node (ref "C6") (pin "1") (pinfunction "1_1") (pintype "passive"))
      (node (ref "C7") (pin "1") (pinfunction "1_1") (pintype "passive"))
      (node (ref "L2") (pin "2") (pinfunction "2_2") (pintype "passive"))
      (node (ref "U3") (pin "10") (pinfunction "PV-_6_10") (pintype "passive"))
      (node (ref "U3") (pin "2") (pinfunction "PV-_1_2") (pintype "passive"))
      (node (ref "U3") (pin "3") (pinfunction "PV-_2_3") (pintype "passive"))
      (node (ref "U3") (pin "7") (pinfunction "PV-_3_7") (pintype "passive"))
      (node (ref "U3") (pin "8") (pinfunction "PV-_4_8") (pintype "passive"))
      (node (ref "U3") (pin "9") (pinfunction "PV-_5_9") (pintype "passive"))
    )
    (net (code "19") (name "Net-(U3-VBST)") (class "Default")
      (node (ref "C2") (pin "1") (pinfunction "1_1") (pintype "passive"))
      (node (ref "U3") (pin "6") (pinfunction "VBST_6") (pintype "passive"))
    )
    (net (code "20") (name "Net-(U3-VCC)") (class "Default")
      (node (ref "C1") (pin "1") (pinfunction "1_1") (pintype "passive"))
      (node (ref "U3") (pin "1") (pinfunction "VCC_1") (pintype "passive"))
    )
    (net (code "21") (name "unconnected-(D1-A_1-Pad1)") (class "Default")
      (node (ref "D1") (pin "1") (pinfunction "A_1_1") (pintype "passive"))
    )
  )
)
